# RadioMusic_F_rev2-1.net
KiCad netlist of a schematic drawn in EAGLE
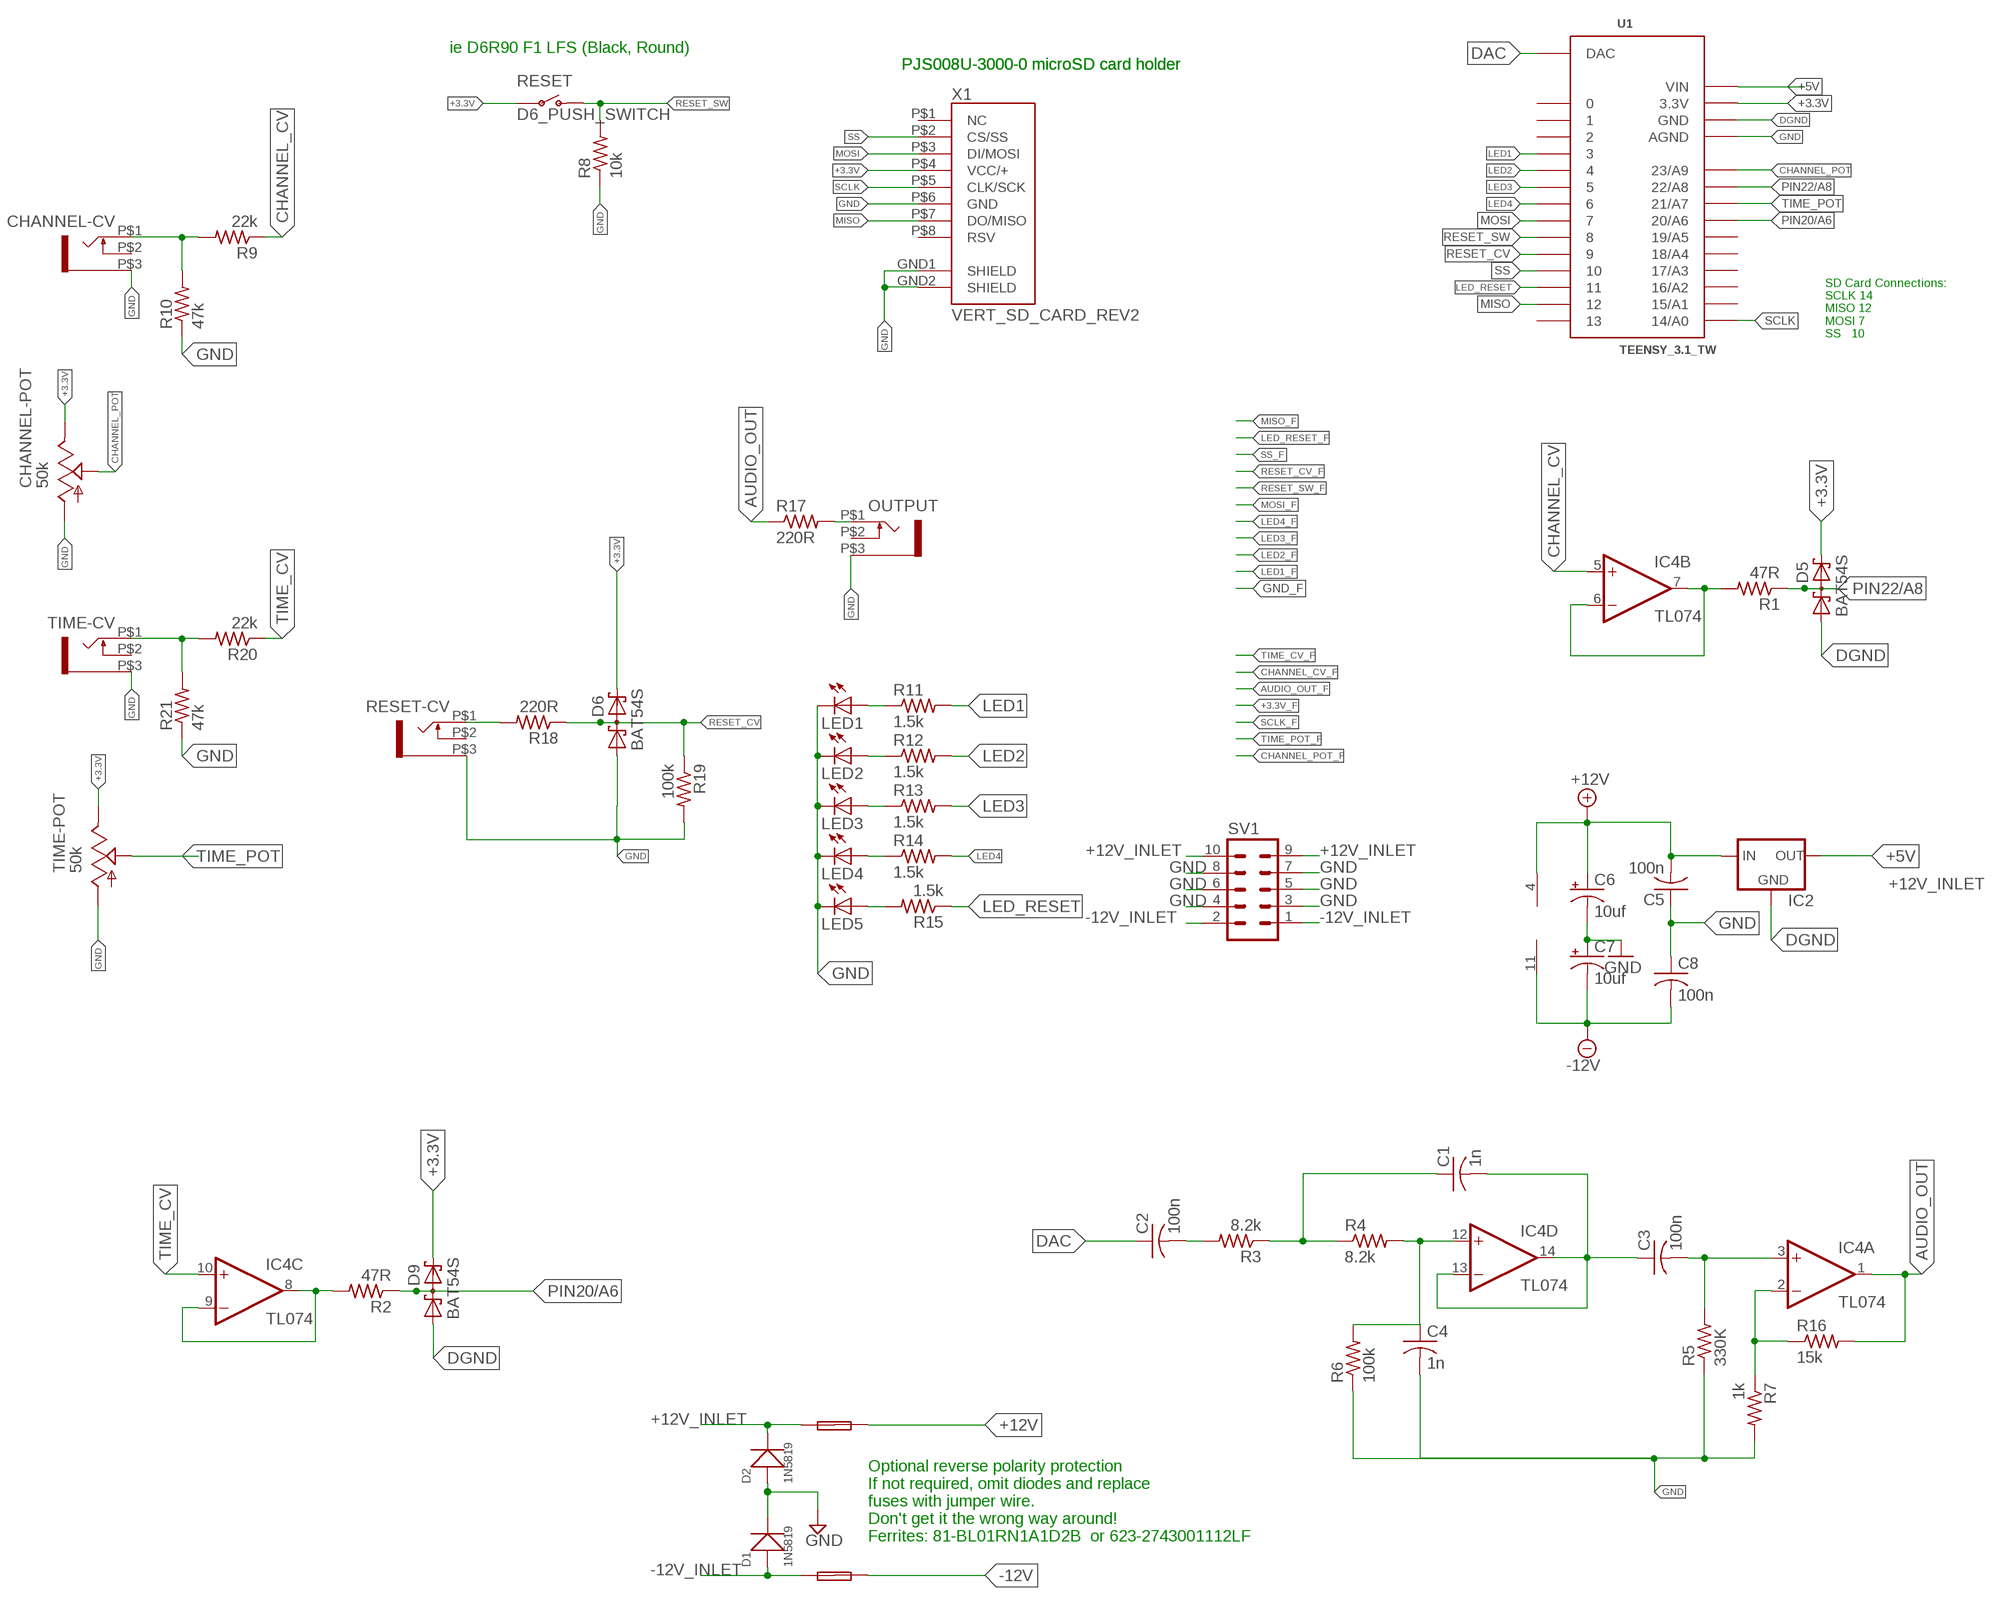
[diagram p0: schematic, sheet 1]

(export (version "E")
  (design (tool "Eeschema 10.0.6"))
  (components
    (comp (ref "C1")
      (value "1n")
      (footprint "eagle-import:C0805")
      (libsource (lib "eagle-import") (part "C-USC0805"))
    )
    (comp (ref "C2")
      (value "100n")
      (footprint "eagle-import:C0805")
      (libsource (lib "eagle-import") (part "C-USC0805"))
    )
    (comp (ref "C3")
      (value "100n")
      (footprint "eagle-import:C0805")
      (libsource (lib "eagle-import") (part "C-USC0805"))
    )
    (comp (ref "C4")
      (value "1n")
      (footprint "eagle-import:C0805")
      (libsource (lib "eagle-import") (part "C-USC0805"))
    )
    (comp (ref "C5")
      (value "100n")
      (footprint "eagle-import:C0805")
      (libsource (lib "eagle-import") (part "C-USC0805"))
    )
    (comp (ref "C6")
      (value "10uf")
      (footprint "eagle-import:CPOL-RADIAL-10UF-25V")
      (libsource (lib "eagle-import") (part "CAP_POLPTH2"))
    )
    (comp (ref "C7")
      (value "10uf")
      (footprint "eagle-import:CPOL-RADIAL-10UF-25V")
      (libsource (lib "eagle-import") (part "CAP_POLPTH2"))
    )
    (comp (ref "C8")
      (value "100n")
      (footprint "eagle-import:C0805")
      (libsource (lib "eagle-import") (part "C-USC0805"))
    )
    (comp (ref "CHANNEL-CV")
      (value "WQP-PJ301M-12_JACK")
      (footprint "eagle-import:WQP-PJ301M-12_JACK")
      (libsource (lib "eagle-import") (part "WQP-PJ301M-12_JACK"))
    )
    (comp (ref "CHANNEL-POT")
      (value "50k")
      (footprint "eagle-import:EVUF")
      (libsource (lib "eagle-import") (part "ALPHA-9MMAF2"))
    )
    (comp (ref "D1")
      (value "1N5819")
      (footprint "eagle-import:SOD-123")
      (fields (field (name "MPN") "B0540W"))
      (libsource (lib "eagle-import") (part "SMD-DIODE-SCHOTTKY-40V-500MA(SOD-123)"))
    )
    (comp (ref "D2")
      (value "1N5819")
      (footprint "eagle-import:SOD-123")
      (fields (field (name "MPN") "B0540W"))
      (libsource (lib "eagle-import") (part "SMD-DIODE-SCHOTTKY-40V-500MA(SOD-123)"))
    )
    (comp (ref "D5")
      (value "BAT54S")
      (footprint "eagle-import:SOT23")
      (libsource (lib "eagle-import") (part "BAT54S"))
    )
    (comp (ref "D6")
      (value "BAT54S")
      (footprint "eagle-import:SOT23")
      (libsource (lib "eagle-import") (part "BAT54S"))
    )
    (comp (ref "D9")
      (value "BAT54S")
      (footprint "eagle-import:SOT23")
      (libsource (lib "eagle-import") (part "BAT54S"))
    )
    (comp (ref "F1")
      (value "FUSE")
      (footprint "eagle-import:C050H075X075")
      (libsource (lib "eagle-import") (part "PTC_FUSEPOLY_FUSE"))
    )
    (comp (ref "F2")
      (value "FUSE")
      (footprint "eagle-import:C050H075X075")
      (libsource (lib "eagle-import") (part "PTC_FUSEPOLY_FUSE"))
    )
    (comp (ref "IC2")
      (value "78LXX")
      (footprint "eagle-import:78LXX")
      (libsource (lib "eagle-import") (part "78LXX"))
    )
    (comp (ref "IC4")
      (value "TL074")
      (footprint "eagle-import:SO14")
      (libsource (lib "eagle-import") (part "TL074D"))
    )
    (comp (ref "LED1")
      (value "LED3MM")
      (footprint "eagle-import:LED3MM")
      (libsource (lib "eagle-import") (part "LED3MM"))
    )
    (comp (ref "LED2")
      (value "LED3MM")
      (footprint "eagle-import:LED3MM")
      (libsource (lib "eagle-import") (part "LED3MM"))
    )
    (comp (ref "LED3")
      (value "LED3MM")
      (footprint "eagle-import:LED3MM")
      (libsource (lib "eagle-import") (part "LED3MM"))
    )
    (comp (ref "LED4")
      (value "LED3MM")
      (footprint "eagle-import:LED3MM")
      (libsource (lib "eagle-import") (part "LED3MM"))
    )
    (comp (ref "LED5")
      (value "LED3MM")
      (footprint "eagle-import:LED3MM")
      (libsource (lib "eagle-import") (part "LED3MM"))
    )
    (comp (ref "OUTPUT")
      (value "WQP-PJ301M-12_JACK")
      (footprint "eagle-import:WQP-PJ301M-12_JACK")
      (libsource (lib "eagle-import") (part "WQP-PJ301M-12_JACK"))
    )
    (comp (ref "R1")
      (value "47R")
      (footprint "eagle-import:R0805")
      (libsource (lib "eagle-import") (part "R-US_R0805"))
    )
    (comp (ref "R2")
      (value "47R")
      (footprint "eagle-import:R0805")
      (libsource (lib "eagle-import") (part "R-US_R0805"))
    )
    (comp (ref "R3")
      (value "8.2k")
      (footprint "eagle-import:R0805")
      (libsource (lib "eagle-import") (part "R-US_R0805"))
    )
    (comp (ref "R4")
      (value "8.2k")
      (footprint "eagle-import:R0805")
      (libsource (lib "eagle-import") (part "R-US_R0805"))
    )
    (comp (ref "R5")
      (value "330K")
      (footprint "eagle-import:R0805")
      (libsource (lib "eagle-import") (part "R-US_R0805"))
    )
    (comp (ref "R6")
      (value "100k")
      (footprint "eagle-import:R0805")
      (libsource (lib "eagle-import") (part "R-US_R0805"))
    )
    (comp (ref "R7")
      (value "1k")
      (footprint "eagle-import:R0805")
      (libsource (lib "eagle-import") (part "R-US_R0805"))
    )
    (comp (ref "R8")
      (value "10k")
      (footprint "eagle-import:R0805")
      (libsource (lib "eagle-import") (part "R-US_R0805"))
    )
    (comp (ref "R9")
      (value "22k")
      (footprint "eagle-import:R0805")
      (libsource (lib "eagle-import") (part "R-US_R0805"))
    )
    (comp (ref "R10")
      (value "47k")
      (footprint "eagle-import:R0805")
      (libsource (lib "eagle-import") (part "R-US_R0805"))
    )
    (comp (ref "R11")
      (value "1.5k")
      (footprint "eagle-import:R0805")
      (libsource (lib "eagle-import") (part "R-US_R0805"))
    )
    (comp (ref "R12")
      (value "1.5k")
      (footprint "eagle-import:R0805")
      (libsource (lib "eagle-import") (part "R-US_R0805"))
    )
    (comp (ref "R13")
      (value "1.5k")
      (footprint "eagle-import:R0805")
      (libsource (lib "eagle-import") (part "R-US_R0805"))
    )
    (comp (ref "R14")
      (value "1.5k")
      (footprint "eagle-import:R0805")
      (libsource (lib "eagle-import") (part "R-US_R0805"))
    )
    (comp (ref "R15")
      (value "1.5k")
      (footprint "eagle-import:R0805")
      (libsource (lib "eagle-import") (part "R-US_R0805"))
    )
    (comp (ref "R16")
      (value "15k")
      (footprint "eagle-import:R0805")
      (libsource (lib "eagle-import") (part "R-US_R0805"))
    )
    (comp (ref "R17")
      (value "220R")
      (footprint "eagle-import:R0805")
      (libsource (lib "eagle-import") (part "R-US_R0805"))
    )
    (comp (ref "R18")
      (value "220R")
      (footprint "eagle-import:R0805")
      (libsource (lib "eagle-import") (part "R-US_R0805"))
    )
    (comp (ref "R19")
      (value "100k")
      (footprint "eagle-import:R0805")
      (libsource (lib "eagle-import") (part "R-US_R0805"))
    )
    (comp (ref "R20")
      (value "22k")
      (footprint "eagle-import:R0805")
      (libsource (lib "eagle-import") (part "R-US_R0805"))
    )
    (comp (ref "R21")
      (value "47k")
      (footprint "eagle-import:R0805")
      (libsource (lib "eagle-import") (part "R-US_R0805"))
    )
    (comp (ref "RESET")
      (value "D6_PUSH_SWITCH")
      (footprint "eagle-import:D6_BUTTON_RND")
      (libsource (lib "eagle-import") (part "D6_PUSH_SWITCH"))
    )
    (comp (ref "RESET-CV")
      (value "WQP-PJ301M-12_JACK")
      (footprint "eagle-import:WQP-PJ301M-12_JACK")
      (libsource (lib "eagle-import") (part "WQP-PJ301M-12_JACK"))
    )
    (comp (ref "SV1")
      (value "10_PIN_HEADER")
      (footprint "eagle-import:MA05-2")
      (libsource (lib "eagle-import") (part "10_PIN_HEADER"))
    )
    (comp (ref "TIME-CV")
      (value "WQP-PJ301M-12_JACK")
      (footprint "eagle-import:WQP-PJ301M-12_JACK")
      (libsource (lib "eagle-import") (part "WQP-PJ301M-12_JACK"))
    )
    (comp (ref "TIME-POT")
      (value "50k")
      (footprint "eagle-import:EVUF")
      (libsource (lib "eagle-import") (part "ALPHA-9MMAF2"))
    )
    (comp (ref "U1")
      (value "TEENSY_3.1_TW")
      (footprint "eagle-import:TEENSY_3.1_TW")
      (libsource (lib "eagle-import") (part "TEENSY_3.1_TW"))
    )
    (comp (ref "X1")
      (value "VERT_SD_CARD_REV2")
      (footprint "eagle-import:VERT_MICROSD_REV2")
      (libsource (lib "eagle-import") (part "VERT_SD_CARD_REV2"))
    )
  )
  (nets
    (net (code "1") (name "+3.3V") (class "Default")
      (node (ref "CHANNEL-POT") (pin "3") (pinfunction "E_3") (pintype "passive"))
      (node (ref "D5") (pin "2") (pinfunction "C2_2") (pintype "passive"))
      (node (ref "D6") (pin "2") (pinfunction "C2_2") (pintype "passive"))
      (node (ref "D9") (pin "2") (pinfunction "C2_2") (pintype "passive"))
      (node (ref "RESET") (pin "P$3") (pinfunction "P_P$3") (pintype "passive"))
      (node (ref "RESET") (pin "P$4") (pinfunction "P_P$4") (pintype "passive"))
      (node (ref "TIME-POT") (pin "3") (pinfunction "E_3") (pintype "passive"))
      (node (ref "U1") (pin "3.3V") (pinfunction "3.3V_3.3V") (pintype "power_in"))
      (node (ref "X1") (pin "P$4") (pinfunction "VCC/+_P$4") (pintype "bidirectional"))
    )
    (net (code "3") (name "+5V") (class "Default")
      (node (ref "IC2") (pin "OUT") (pinfunction "OUT_OUT") (pintype "passive"))
      (node (ref "U1") (pin "VIN") (pinfunction "VIN_VIN") (pintype "power_in"))
    )
    (net (code "4") (name "+12V") (class "Default")
      (node (ref "C5") (pin "2") (pinfunction "2_2") (pintype "passive"))
      (node (ref "C6") (pin "1") (pinfunction "+_1") (pintype "passive"))
      (node (ref "F1") (pin "2") (pinfunction "P$2_2") (pintype "bidirectional"))
      (node (ref "IC2") (pin "IN") (pinfunction "IN_IN") (pintype "input"))
      (node (ref "IC4") (pin "4") (pinfunction "V+_4") (pintype "power_in"))
    )
    (net (code "5") (name "-12V") (class "Default")
      (node (ref "C7") (pin "2") (pinfunction "-_2") (pintype "passive"))
      (node (ref "C8") (pin "2") (pinfunction "2_2") (pintype "passive"))
      (node (ref "F2") (pin "2") (pinfunction "P$2_2") (pintype "bidirectional"))
      (node (ref "IC4") (pin "11") (pinfunction "V-_11") (pintype "power_in"))
    )
    (net (code "6") (name "/+12V_INLET") (class "Default")
      (node (ref "D2") (pin "-") (pinfunction "-_-") (pintype "passive"))
      (node (ref "F1") (pin "1") (pinfunction "P$1_1") (pintype "bidirectional"))
      (node (ref "SV1") (pin "10") (pinfunction "10_10") (pintype "passive"))
      (node (ref "SV1") (pin "9") (pinfunction "9_9") (pintype "passive"))
    )
    (net (code "7") (name "/-12V_INLET") (class "Default")
      (node (ref "D1") (pin "+") (pinfunction "+_+") (pintype "passive"))
      (node (ref "F2") (pin "1") (pinfunction "P$1_1") (pintype "bidirectional"))
      (node (ref "SV1") (pin "1") (pinfunction "1_1") (pintype "passive"))
      (node (ref "SV1") (pin "2") (pinfunction "2_2") (pintype "passive"))
    )
    (net (code "8") (name "AUDIO_OUT") (class "Default")
      (node (ref "IC4") (pin "1") (pinfunction "OUT_1") (pintype "output"))
      (node (ref "R16") (pin "2") (pinfunction "2_2") (pintype "passive"))
      (node (ref "R17") (pin "1") (pinfunction "1_1") (pintype "passive"))
    )
    (net (code "10") (name "CHANNEL_CV") (class "Default")
      (node (ref "IC4") (pin "5") (pinfunction "+IN_5") (pintype "input"))
      (node (ref "R9") (pin "1") (pinfunction "1_1") (pintype "passive"))
    )
    (net (code "12") (name "CHANNEL_POT") (class "Default")
      (node (ref "CHANNEL-POT") (pin "2") (pinfunction "S_2") (pintype "passive"))
      (node (ref "U1") (pin "23/A9") (pinfunction "23/A9_23/A9") (pintype "bidirectional"))
    )
    (net (code "14") (name "DAC") (class "Default")
      (node (ref "C2") (pin "1") (pinfunction "1_1") (pintype "passive"))
      (node (ref "U1") (pin "DAC") (pinfunction "DAC_DAC") (pintype "bidirectional"))
    )
    (net (code "15") (name "DGND") (class "Default")
      (node (ref "D5") (pin "1") (pinfunction "A1_1") (pintype "passive"))
      (node (ref "D9") (pin "1") (pinfunction "A1_1") (pintype "passive"))
      (node (ref "IC2") (pin "GND") (pinfunction "GND_GND") (pintype "input"))
      (node (ref "U1") (pin "GND") (pinfunction "GND_GND") (pintype "power_in"))
    )
    (net (code "16") (name "GND") (class "Default")
      (node (ref "C4") (pin "2") (pinfunction "2_2") (pintype "passive"))
      (node (ref "C5") (pin "1") (pinfunction "1_1") (pintype "passive"))
      (node (ref "C6") (pin "2") (pinfunction "-_2") (pintype "passive"))
      (node (ref "C7") (pin "1") (pinfunction "+_1") (pintype "passive"))
      (node (ref "C8") (pin "1") (pinfunction "1_1") (pintype "passive"))
      (node (ref "CHANNEL-CV") (pin "P$3") (pinfunction "1_P$3") (pintype "passive"))
      (node (ref "CHANNEL-POT") (pin "1") (pinfunction "A_1") (pintype "passive"))
      (node (ref "D1") (pin "-") (pinfunction "-_-") (pintype "passive"))
      (node (ref "D2") (pin "+") (pinfunction "+_+") (pintype "passive"))
      (node (ref "D6") (pin "1") (pinfunction "A1_1") (pintype "passive"))
      (node (ref "LED1") (pin "K") (pinfunction "C_K") (pintype "passive"))
      (node (ref "LED2") (pin "K") (pinfunction "C_K") (pintype "passive"))
      (node (ref "LED3") (pin "K") (pinfunction "C_K") (pintype "passive"))
      (node (ref "LED4") (pin "K") (pinfunction "C_K") (pintype "passive"))
      (node (ref "LED5") (pin "K") (pinfunction "C_K") (pintype "passive"))
      (node (ref "OUTPUT") (pin "P$3") (pinfunction "1_P$3") (pintype "passive"))
      (node (ref "R10") (pin "1") (pinfunction "1_1") (pintype "passive"))
      (node (ref "R19") (pin "2") (pinfunction "2_2") (pintype "passive"))
      (node (ref "R21") (pin "1") (pinfunction "1_1") (pintype "passive"))
      (node (ref "R5") (pin "1") (pinfunction "1_1") (pintype "passive"))
      (node (ref "R6") (pin "1") (pinfunction "1_1") (pintype "passive"))
      (node (ref "R7") (pin "2") (pinfunction "2_2") (pintype "passive"))
      (node (ref "R8") (pin "1") (pinfunction "1_1") (pintype "passive"))
      (node (ref "RESET-CV") (pin "P$3") (pinfunction "1_P$3") (pintype "passive"))
      (node (ref "SV1") (pin "3") (pinfunction "3_3") (pintype "passive"))
      (node (ref "SV1") (pin "4") (pinfunction "4_4") (pintype "passive"))
      (node (ref "SV1") (pin "5") (pinfunction "5_5") (pintype "passive"))
      (node (ref "SV1") (pin "6") (pinfunction "6_6") (pintype "passive"))
      (node (ref "SV1") (pin "7") (pinfunction "7_7") (pintype "passive"))
      (node (ref "SV1") (pin "8") (pinfunction "8_8") (pintype "passive"))
      (node (ref "TIME-CV") (pin "P$3") (pinfunction "1_P$3") (pintype "passive"))
      (node (ref "TIME-POT") (pin "1") (pinfunction "A_1") (pintype "passive"))
      (node (ref "U1") (pin "AGND") (pinfunction "AGND_AGND") (pintype "power_in"))
      (node (ref "X1") (pin "GND1") (pinfunction "SHIELD_GND1") (pintype "bidirectional"))
      (node (ref "X1") (pin "GND2") (pinfunction "SHIELD_GND2") (pintype "bidirectional"))
      (node (ref "X1") (pin "P$6") (pinfunction "GND_P$6") (pintype "bidirectional"))
    )
    (net (code "18") (name "LED1") (class "Default")
      (node (ref "R11") (pin "2") (pinfunction "2_2") (pintype "passive"))
      (node (ref "U1") (pin "3") (pinfunction "3_3") (pintype "bidirectional"))
    )
    (net (code "20") (name "LED2") (class "Default")
      (node (ref "R12") (pin "2") (pinfunction "2_2") (pintype "passive"))
      (node (ref "U1") (pin "4") (pinfunction "4_4") (pintype "bidirectional"))
    )
    (net (code "22") (name "LED3") (class "Default")
      (node (ref "R13") (pin "2") (pinfunction "2_2") (pintype "passive"))
      (node (ref "U1") (pin "5") (pinfunction "5_5") (pintype "bidirectional"))
    )
    (net (code "24") (name "LED4") (class "Default")
      (node (ref "R14") (pin "2") (pinfunction "2_2") (pintype "passive"))
      (node (ref "U1") (pin "6") (pinfunction "6_6") (pintype "bidirectional"))
    )
    (net (code "26") (name "LED_RESET") (class "Default")
      (node (ref "R15") (pin "1") (pinfunction "1_1") (pintype "passive"))
      (node (ref "U1") (pin "11") (pinfunction "11_11") (pintype "bidirectional"))
    )
    (net (code "28") (name "MISO") (class "Default")
      (node (ref "U1") (pin "12") (pinfunction "12_12") (pintype "bidirectional"))
      (node (ref "X1") (pin "P$7") (pinfunction "DO/MISO_P$7") (pintype "bidirectional"))
    )
    (net (code "30") (name "MOSI") (class "Default")
      (node (ref "U1") (pin "7") (pinfunction "7_7") (pintype "bidirectional"))
      (node (ref "X1") (pin "P$3") (pinfunction "DI/MOSI_P$3") (pintype "bidirectional"))
    )
    (net (code "32") (name "Net-(C1-Pad1)") (class "Default")
      (node (ref "C1") (pin "1") (pinfunction "1_1") (pintype "passive"))
      (node (ref "R3") (pin "1") (pinfunction "1_1") (pintype "passive"))
      (node (ref "R4") (pin "1") (pinfunction "1_1") (pintype "passive"))
    )
    (net (code "33") (name "Net-(C2-Pad2)") (class "Default")
      (node (ref "C2") (pin "2") (pinfunction "2_2") (pintype "passive"))
      (node (ref "R3") (pin "2") (pinfunction "2_2") (pintype "passive"))
    )
    (net (code "34") (name "Net-(CHANNEL-CV-2)") (class "Default")
      (node (ref "CHANNEL-CV") (pin "P$1") (pinfunction "2_P$1") (pintype "passive"))
      (node (ref "R10") (pin "2") (pinfunction "2_2") (pintype "passive"))
      (node (ref "R9") (pin "2") (pinfunction "2_2") (pintype "passive"))
    )
    (net (code "35") (name "Net-(IC4A-+IN)") (class "Default")
      (node (ref "C3") (pin "2") (pinfunction "2_2") (pintype "passive"))
      (node (ref "IC4") (pin "3") (pinfunction "+IN_3") (pintype "input"))
      (node (ref "R5") (pin "2") (pinfunction "2_2") (pintype "passive"))
    )
    (net (code "36") (name "Net-(IC4A--IN)") (class "Default")
      (node (ref "IC4") (pin "2") (pinfunction "-IN_2") (pintype "input"))
      (node (ref "R16") (pin "1") (pinfunction "1_1") (pintype "passive"))
      (node (ref "R7") (pin "1") (pinfunction "1_1") (pintype "passive"))
    )
    (net (code "37") (name "Net-(IC4B--IN)") (class "Default")
      (node (ref "IC4") (pin "6") (pinfunction "-IN_6") (pintype "input"))
      (node (ref "IC4") (pin "7") (pinfunction "OUT_7") (pintype "output"))
      (node (ref "R1") (pin "2") (pinfunction "2_2") (pintype "passive"))
    )
    (net (code "38") (name "Net-(IC4C--IN)") (class "Default")
      (node (ref "IC4") (pin "8") (pinfunction "OUT_8") (pintype "output"))
      (node (ref "IC4") (pin "9") (pinfunction "-IN_9") (pintype "input"))
      (node (ref "R2") (pin "2") (pinfunction "2_2") (pintype "passive"))
    )
    (net (code "39") (name "Net-(IC4D-+IN)") (class "Default")
      (node (ref "C4") (pin "1") (pinfunction "1_1") (pintype "passive"))
      (node (ref "IC4") (pin "12") (pinfunction "+IN_12") (pintype "input"))
      (node (ref "R4") (pin "2") (pinfunction "2_2") (pintype "passive"))
      (node (ref "R6") (pin "2") (pinfunction "2_2") (pintype "passive"))
    )
    (net (code "40") (name "Net-(IC4D--IN)") (class "Default")
      (node (ref "C1") (pin "2") (pinfunction "2_2") (pintype "passive"))
      (node (ref "C3") (pin "1") (pinfunction "1_1") (pintype "passive"))
      (node (ref "IC4") (pin "13") (pinfunction "-IN_13") (pintype "input"))
      (node (ref "IC4") (pin "14") (pinfunction "OUT_14") (pintype "output"))
    )
    (net (code "41") (name "Net-(LED1-PadA)") (class "Default")
      (node (ref "LED1") (pin "A") (pinfunction "A_A") (pintype "passive"))
      (node (ref "R11") (pin "1") (pinfunction "1_1") (pintype "passive"))
    )
    (net (code "42") (name "Net-(LED2-PadA)") (class "Default")
      (node (ref "LED2") (pin "A") (pinfunction "A_A") (pintype "passive"))
      (node (ref "R12") (pin "1") (pinfunction "1_1") (pintype "passive"))
    )
    (net (code "43") (name "Net-(LED3-PadA)") (class "Default")
      (node (ref "LED3") (pin "A") (pinfunction "A_A") (pintype "passive"))
      (node (ref "R13") (pin "1") (pinfunction "1_1") (pintype "passive"))
    )
    (net (code "44") (name "Net-(LED4-PadA)") (class "Default")
      (node (ref "LED4") (pin "A") (pinfunction "A_A") (pintype "passive"))
      (node (ref "R14") (pin "1") (pinfunction "1_1") (pintype "passive"))
    )
    (net (code "45") (name "Net-(LED5-PadA)") (class "Default")
      (node (ref "LED5") (pin "A") (pinfunction "A_A") (pintype "passive"))
      (node (ref "R15") (pin "2") (pinfunction "2_2") (pintype "passive"))
    )
    (net (code "46") (name "Net-(OUTPUT-2)") (class "Default")
      (node (ref "OUTPUT") (pin "P$1") (pinfunction "2_P$1") (pintype "passive"))
      (node (ref "R17") (pin "2") (pinfunction "2_2") (pintype "passive"))
    )
    (net (code "47") (name "Net-(RESET-CV-2)") (class "Default")
      (node (ref "R18") (pin "2") (pinfunction "2_2") (pintype "passive"))
      (node (ref "RESET-CV") (pin "P$1") (pinfunction "2_P$1") (pintype "passive"))
    )
    (net (code "48") (name "Net-(TIME-CV-2)") (class "Default")
      (node (ref "R20") (pin "2") (pinfunction "2_2") (pintype "passive"))
      (node (ref "R21") (pin "2") (pinfunction "2_2") (pintype "passive"))
      (node (ref "TIME-CV") (pin "P$1") (pinfunction "2_P$1") (pintype "passive"))
    )
    (net (code "49") (name "PIN20{slash}A6") (class "Default")
      (node (ref "D9") (pin "3") (pinfunction "C1A2_3") (pintype "passive"))
      (node (ref "R2") (pin "1") (pinfunction "1_1") (pintype "passive"))
      (node (ref "U1") (pin "20/A6") (pinfunction "20/A6_20/A6") (pintype "bidirectional"))
    )
    (net (code "50") (name "PIN22{slash}A8") (class "Default")
      (node (ref "D5") (pin "3") (pinfunction "C1A2_3") (pintype "passive"))
      (node (ref "R1") (pin "1") (pinfunction "1_1") (pintype "passive"))
      (node (ref "U1") (pin "22/A8") (pinfunction "22/A8_22/A8") (pintype "bidirectional"))
    )
    (net (code "51") (name "RESET_CV") (class "Default")
      (node (ref "D6") (pin "3") (pinfunction "C1A2_3") (pintype "passive"))
      (node (ref "R18") (pin "1") (pinfunction "1_1") (pintype "passive"))
      (node (ref "R19") (pin "1") (pinfunction "1_1") (pintype "passive"))
      (node (ref "U1") (pin "9") (pinfunction "9_9") (pintype "bidirectional"))
    )
    (net (code "53") (name "RESET_SW") (class "Default")
      (node (ref "R8") (pin "2") (pinfunction "2_2") (pintype "passive"))
      (node (ref "RESET") (pin "P$1") (pinfunction "O_P$1") (pintype "passive"))
      (node (ref "RESET") (pin "P$2") (pinfunction "O_P$2") (pintype "passive"))
      (node (ref "U1") (pin "8") (pinfunction "8_8") (pintype "bidirectional"))
    )
    (net (code "55") (name "SCLK") (class "Default")
      (node (ref "U1") (pin "14/A0") (pinfunction "14/A0_14/A0") (pintype "bidirectional"))
      (node (ref "X1") (pin "P$5") (pinfunction "CLK/SCK_P$5") (pintype "bidirectional"))
    )
    (net (code "57") (name "SS") (class "Default")
      (node (ref "U1") (pin "10") (pinfunction "10_10") (pintype "bidirectional"))
      (node (ref "X1") (pin "P$2") (pinfunction "CS/SS_P$2") (pintype "bidirectional"))
    )
    (net (code "59") (name "TIME_CV") (class "Default")
      (node (ref "IC4") (pin "10") (pinfunction "+IN_10") (pintype "input"))
      (node (ref "R20") (pin "1") (pinfunction "1_1") (pintype "passive"))
    )
    (net (code "61") (name "TIME_POT") (class "Default")
      (node (ref "TIME-POT") (pin "2") (pinfunction "S_2") (pintype "passive"))
      (node (ref "U1") (pin "21/A7") (pinfunction "21/A7_21/A7") (pintype "bidirectional"))
    )
    (net (code "63") (name "unconnected-(CHANNEL-CV-3-PadP$2)") (class "Default")
      (node (ref "CHANNEL-CV") (pin "P$2") (pinfunction "3_P$2") (pintype "passive"))
    )
    (net (code "64") (name "unconnected-(OUTPUT-3-PadP$2)") (class "Default")
      (node (ref "OUTPUT") (pin "P$2") (pinfunction "3_P$2") (pintype "passive"))
    )
    (net (code "65") (name "unconnected-(RESET-CV-3-PadP$2)") (class "Default")
      (node (ref "RESET-CV") (pin "P$2") (pinfunction "3_P$2") (pintype "passive"))
    )
    (net (code "66") (name "unconnected-(TIME-CV-3-PadP$2)") (class "Default")
      (node (ref "TIME-CV") (pin "P$2") (pinfunction "3_P$2") (pintype "passive"))
    )
    (net (code "67") (name "unconnected-(U1-Pad0)") (class "Default")
      (node (ref "U1") (pin "0") (pinfunction "0_0") (pintype "bidirectional"))
    )
    (net (code "68") (name "unconnected-(U1-Pad1)") (class "Default")
      (node (ref "U1") (pin "1") (pinfunction "1_1") (pintype "bidirectional"))
    )
    (net (code "69") (name "unconnected-(U1-Pad2)") (class "Default")
      (node (ref "U1") (pin "2") (pinfunction "2_2") (pintype "bidirectional"))
    )
    (net (code "70") (name "unconnected-(U1-Pad13)") (class "Default")
      (node (ref "U1") (pin "13") (pinfunction "13_13") (pintype "bidirectional"))
    )
    (net (code "71") (name "unconnected-(U1-Pad15{slash}A1)") (class "Default")
      (node (ref "U1") (pin "15/A1") (pinfunction "15/A1_15/A1") (pintype "bidirectional"))
    )
    (net (code "72") (name "unconnected-(U1-Pad16{slash}A2)") (class "Default")
      (node (ref "U1") (pin "16/A2") (pinfunction "16/A2_16/A2") (pintype "bidirectional"))
    )
    (net (code "73") (name "unconnected-(U1-Pad17{slash}A3)") (class "Default")
      (node (ref "U1") (pin "17/A3") (pinfunction "17/A3_17/A3") (pintype "bidirectional"))
    )
    (net (code "74") (name "unconnected-(U1-Pad18{slash}A4)") (class "Default")
      (node (ref "U1") (pin "18/A4") (pinfunction "18/A4_18/A4") (pintype "bidirectional"))
    )
    (net (code "75") (name "unconnected-(U1-Pad19{slash}A5)") (class "Default")
      (node (ref "U1") (pin "19/A5") (pinfunction "19/A5_19/A5") (pintype "bidirectional"))
    )
    (net (code "76") (name "unconnected-(X1-NC-PadP$1)") (class "Default")
      (node (ref "X1") (pin "P$1") (pinfunction "NC_P$1") (pintype "bidirectional"))
    )
    (net (code "77") (name "unconnected-(X1-RSV-PadP$8)") (class "Default")
      (node (ref "X1") (pin "P$8") (pinfunction "RSV_P$8") (pintype "bidirectional"))
    )
  )
)
